# led-flex.net
KiCad netlist of a schematic drawn in EasyEDA
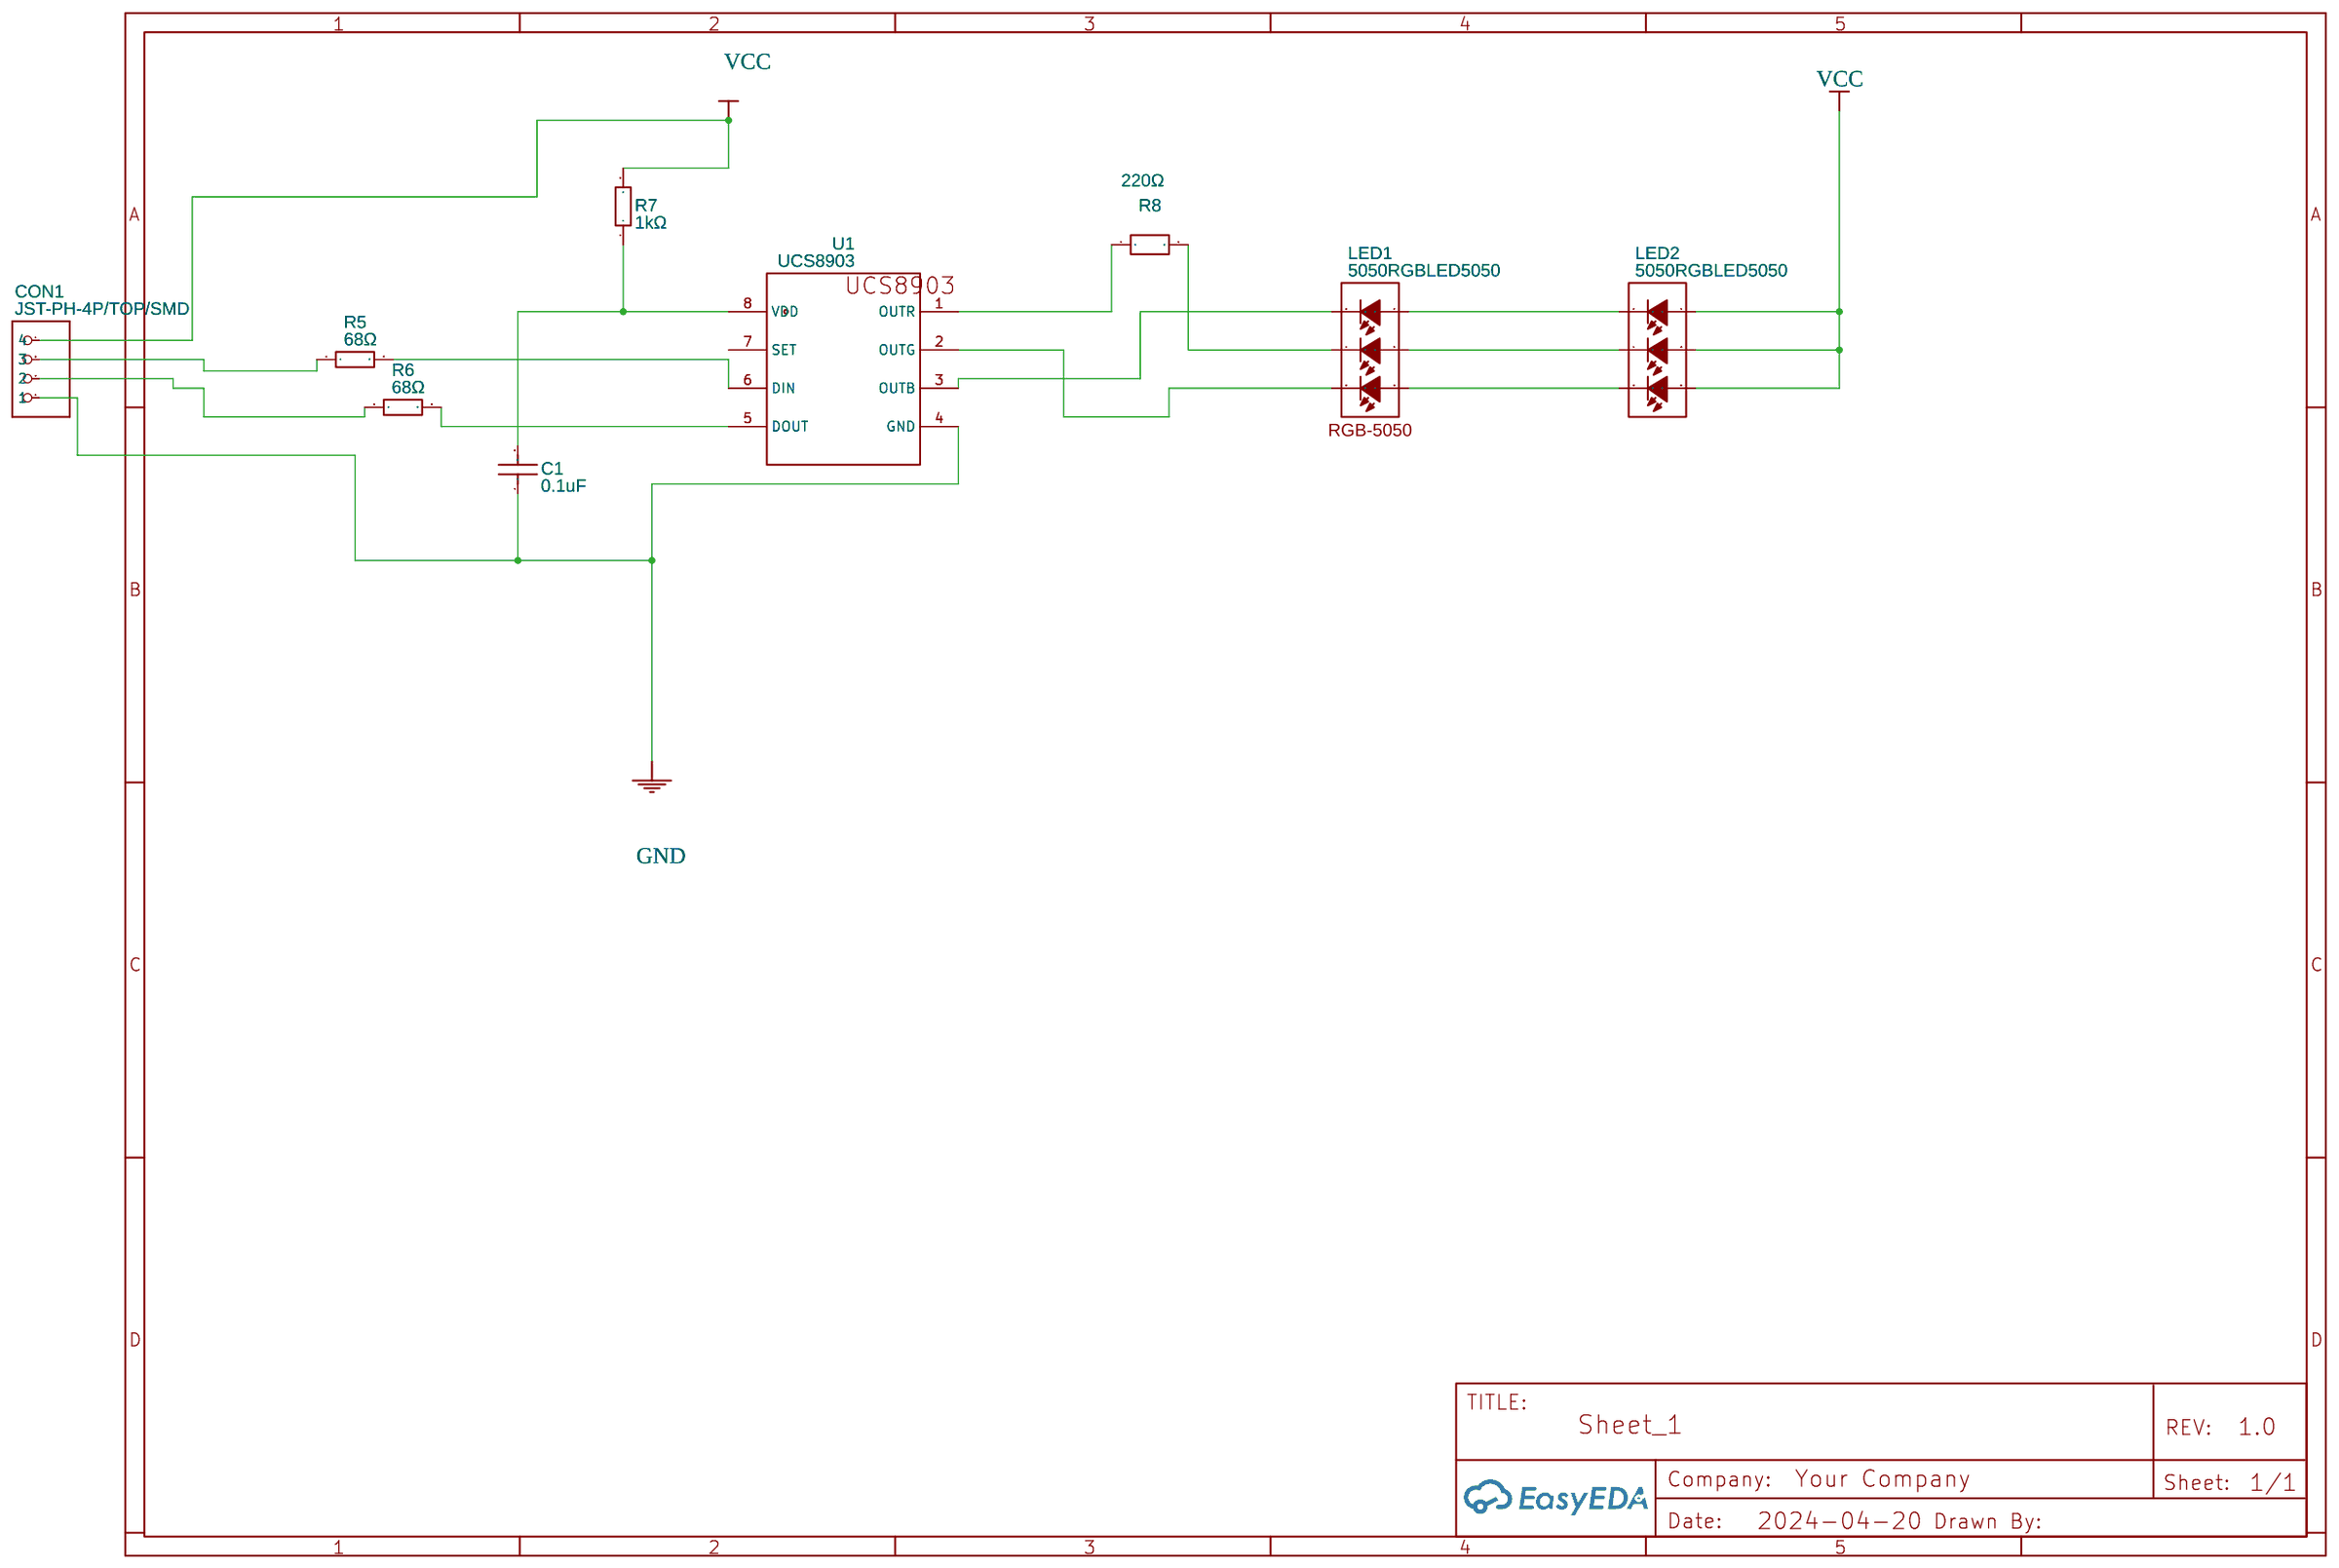
[diagram p0: schematic sheet]

(export (version "E")
  (design (tool "Eeschema 10.0.6"))
  (components
    (comp (ref "C1")
      (value "0.1uF")
      (fields (field (name "Manufacturer Part") "Resisitor MF25 470, 0.25W"))
      (libsource (lib "") (part "KONDENSATOR SMD"))
    )
    (comp (ref "CON1") (value "JST-PH-4P/TOP/SMD") (libsource (lib "") (part "JST-PH-4P/TOP/SMD")))
    (comp (ref "LED1")
      (value "5050RGBLED5050")
      (fields
        (field (name "Manufacturer Part") "5050RGBSMDLEDLamp beads 5050Bright red and blue")
        (field (name "Manufacturer") "ReliaPro")
      )
      (libsource (lib "") (part "5050RGBLED5050_1"))
    )
    (comp (ref "LED2")
      (value "5050RGBLED5050")
      (fields
        (field (name "Manufacturer Part") "5050RGBSMDLEDLamp beads 5050Bright red and blue")
        (field (name "Manufacturer") "ReliaPro")
      )
      (libsource (lib "") (part "5050RGBLED5050"))
    )
    (comp (ref "R5")
      (value "68Ω")
      (fields
        (field (name "Manufacturer Part") "1210W2J0680T5E")
        (field (name "Manufacturer") "UNI-ROYAL(厚声)")
      )
      (libsource (lib "") (part "1210W2J0680T5E"))
    )
    (comp (ref "R6")
      (value "68Ω")
      (fields
        (field (name "Manufacturer Part") "1210W2J0680T5E")
        (field (name "Manufacturer") "UNI-ROYAL(厚声)")
      )
      (libsource (lib "") (part "1210W2J0680T5E"))
    )
    (comp (ref "R7")
      (value "1kΩ")
      (fields (field (name "Manufacturer Part") "RTT12102JTP") (field (name "Manufacturer") "RALEC(旺诠)"))
      (libsource (lib "") (part "RTT12102JTP"))
    )
    (comp (ref "R8")
      (value "220Ω")
      (fields (field (name "Manufacturer Part") "RTT122200FTP") (field (name "Manufacturer") "RALEC(旺诠)"))
      (libsource (lib "") (part "RTT122200FTP"))
    )
    (comp (ref "U1") (value "UCS8903") (libsource (lib "") (part "UCS8903")))
  )
  (nets
    (net (code "1") (name "GND") (class "Default")
      (node (ref "C1") (pin "1") (pinfunction "1_1") (pintype "unspecified"))
      (node (ref "CON1") (pin "1") (pinfunction "1_1") (pintype "bidirectional"))
      (node (ref "U1") (pin "4") (pinfunction "GND_4") (pintype "unspecified"))
    )
    (net (code "2") (name "Net-(CON1-Pad2)") (class "Default")
      (node (ref "CON1") (pin "2") (pinfunction "2_2") (pintype "bidirectional"))
      (node (ref "R6") (pin "1") (pinfunction "1_1") (pintype "unspecified"))
    )
    (net (code "3") (name "Net-(CON1-Pad3)") (class "Default")
      (node (ref "CON1") (pin "3") (pinfunction "3_3") (pintype "bidirectional"))
      (node (ref "R5") (pin "1") (pinfunction "1_1") (pintype "unspecified"))
    )
    (net (code "4") (name "Net-(LED1-A-Pad1)") (class "Default")
      (node (ref "LED1") (pin "1") (pinfunction "A_1") (pintype "unspecified"))
      (node (ref "LED2") (pin "2") (pinfunction "K_2") (pintype "unspecified"))
    )
    (net (code "5") (name "Net-(LED1-A-Pad3)") (class "Default")
      (node (ref "LED1") (pin "3") (pinfunction "A_3") (pintype "unspecified"))
      (node (ref "LED2") (pin "4") (pinfunction "K_4") (pintype "unspecified"))
    )
    (net (code "6") (name "Net-(LED1-A-Pad5)") (class "Default")
      (node (ref "LED1") (pin "5") (pinfunction "A_5") (pintype "unspecified"))
      (node (ref "LED2") (pin "6") (pinfunction "K_6") (pintype "unspecified"))
    )
    (net (code "7") (name "Net-(LED1-K-Pad4)") (class "Default")
      (node (ref "LED1") (pin "4") (pinfunction "K_4") (pintype "unspecified"))
      (node (ref "R8") (pin "2") (pinfunction "2_2") (pintype "unspecified"))
    )
    (net (code "8") (name "Net-(U1-DIN)") (class "Default")
      (node (ref "R5") (pin "2") (pinfunction "2_2") (pintype "unspecified"))
      (node (ref "U1") (pin "6") (pinfunction "DIN_6") (pintype "unspecified"))
    )
    (net (code "9") (name "Net-(U1-DOUT)") (class "Default")
      (node (ref "R6") (pin "2") (pinfunction "2_2") (pintype "unspecified"))
      (node (ref "U1") (pin "5") (pinfunction "DOUT_5") (pintype "unspecified"))
    )
    (net (code "10") (name "Net-(U1-OUTB)") (class "Default")
      (node (ref "LED1") (pin "2") (pinfunction "K_2") (pintype "unspecified"))
      (node (ref "U1") (pin "3") (pinfunction "OUTB_3") (pintype "unspecified"))
    )
    (net (code "11") (name "Net-(U1-OUTG)") (class "Default")
      (node (ref "LED1") (pin "6") (pinfunction "K_6") (pintype "unspecified"))
      (node (ref "U1") (pin "2") (pinfunction "OUTG_2") (pintype "unspecified"))
    )
    (net (code "12") (name "Net-(U1-OUTR)") (class "Default")
      (node (ref "R8") (pin "1") (pinfunction "1_1") (pintype "unspecified"))
      (node (ref "U1") (pin "1") (pinfunction "OUTR_1") (pintype "unspecified"))
    )
    (net (code "13") (name "Net-(U1-VDD)") (class "Default")
      (node (ref "C1") (pin "2") (pinfunction "2_2") (pintype "unspecified"))
      (node (ref "R7") (pin "1") (pinfunction "1_1") (pintype "input"))
      (node (ref "U1") (pin "8") (pinfunction "VDD_8") (pintype "unspecified"))
    )
    (net (code "14") (name "VCC") (class "Default")
      (node (ref "CON1") (pin "4") (pinfunction "4_4") (pintype "bidirectional"))
      (node (ref "LED2") (pin "1") (pinfunction "A_1") (pintype "unspecified"))
      (node (ref "LED2") (pin "3") (pinfunction "A_3") (pintype "unspecified"))
      (node (ref "LED2") (pin "5") (pinfunction "A_5") (pintype "unspecified"))
      (node (ref "R7") (pin "2") (pinfunction "2_2") (pintype "input"))
    )
    (net (code "15") (name "unconnected-(U1-SET-Pad7)") (class "Default")
      (node (ref "U1") (pin "7") (pinfunction "SET_7") (pintype "unspecified"))
    )
  )
)
